# SCH_blinking-lights_2025-11-07.net
KiCad netlist of a schematic drawn in EasyEDA
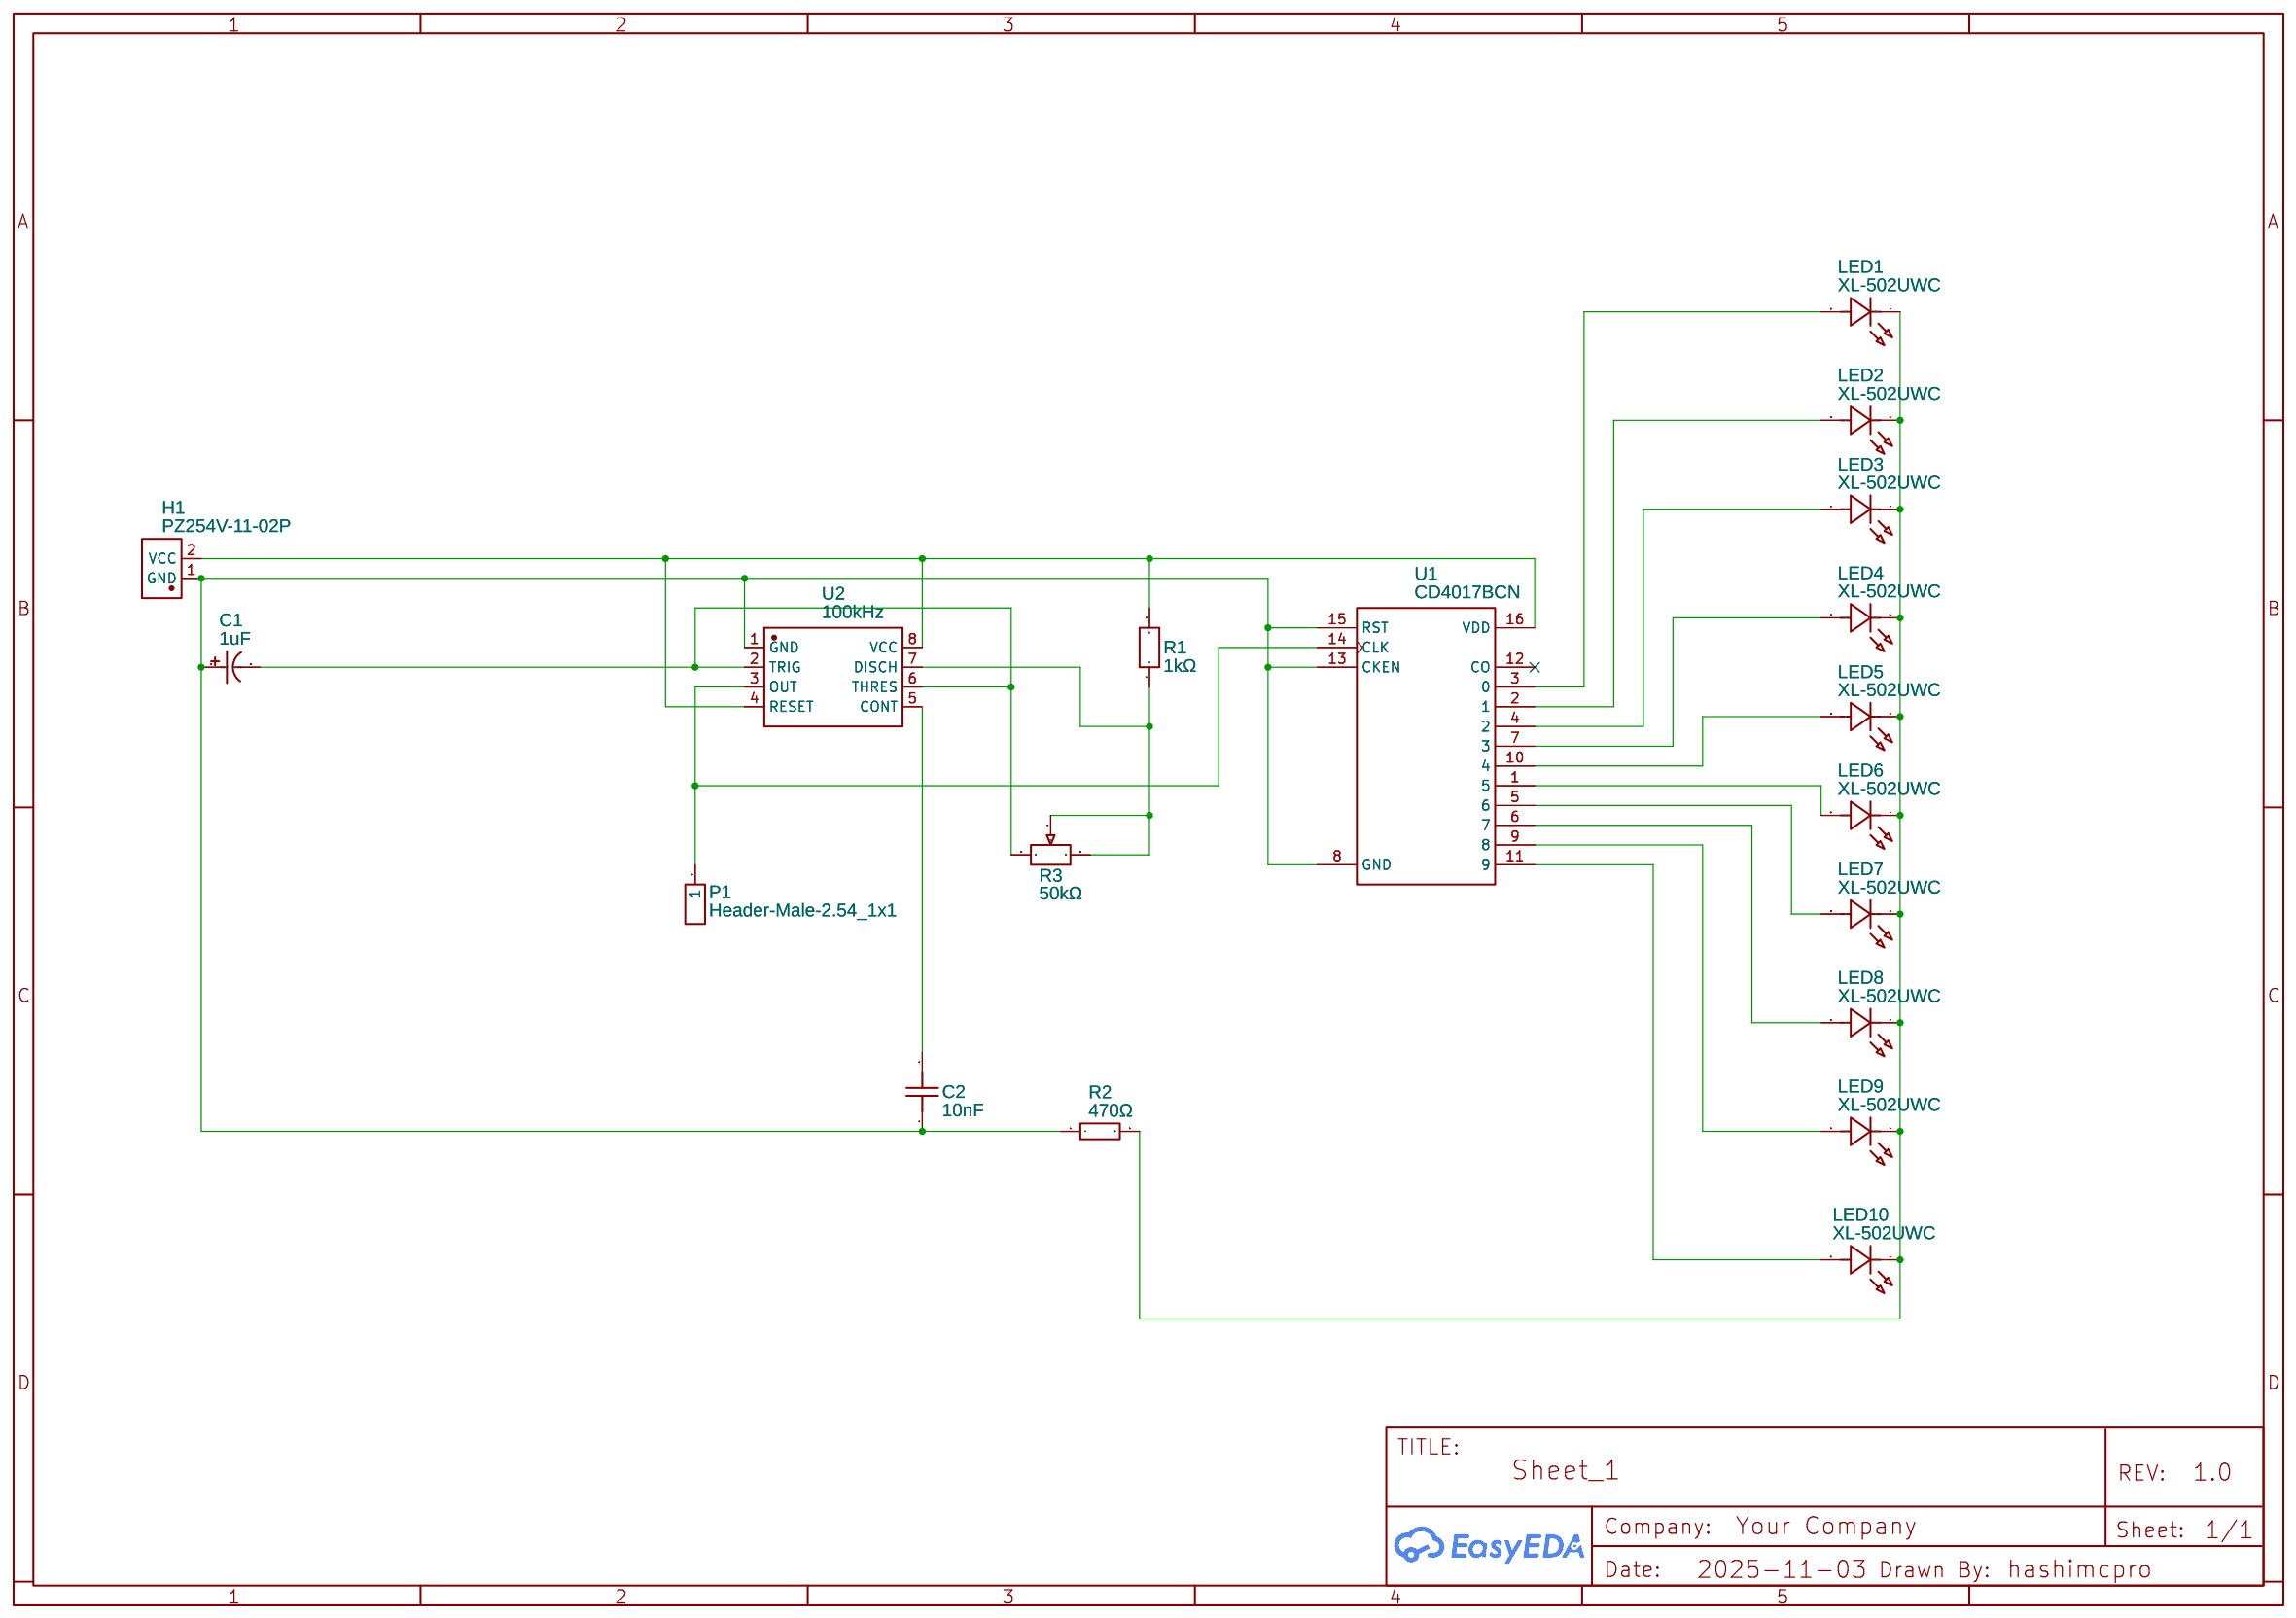
[diagram p0: schematic sheet]

(export (version "E")
  (design (tool "Eeschema 10.0.6"))
  (components
    (comp (ref "C1")
      (value "1uF")
      (fields (field (name "Manufacturer Part") "KF010M050C110A") (field (name "Manufacturer") "CapXon(丰宾)"))
      (libsource (lib "") (part "KF010M050C110A"))
    )
    (comp (ref "C2")
      (value "10nF")
      (fields (field (name "Manufacturer Part") "N09F1B103MN0B0S0N0") (field (name "Manufacturer") "STE(松田)"))
      (libsource (lib "") (part "N09F1B103MN0B0S0N0"))
    )
    (comp (ref "H1")
      (value "PZ254V-11-02P")
      (fields (field (name "Manufacturer") "XFCN(兴飞)"))
      (libsource (lib "") (part "PZ254V-11-02P"))
    )
    (comp (ref "LED1")
      (value "XL-502UWC")
      (fields (field (name "Manufacturer") "XINGLIGHT(成兴光)"))
      (libsource (lib "") (part "XL-502UWC"))
    )
    (comp (ref "LED2")
      (value "XL-502UWC")
      (fields (field (name "Manufacturer") "XINGLIGHT(成兴光)"))
      (libsource (lib "") (part "XL-502UWC"))
    )
    (comp (ref "LED3")
      (value "XL-502UWC")
      (fields (field (name "Manufacturer") "XINGLIGHT(成兴光)"))
      (libsource (lib "") (part "XL-502UWC"))
    )
    (comp (ref "LED4")
      (value "XL-502UWC")
      (fields (field (name "Manufacturer") "XINGLIGHT(成兴光)"))
      (libsource (lib "") (part "XL-502UWC"))
    )
    (comp (ref "LED5")
      (value "XL-502UWC")
      (fields (field (name "Manufacturer") "XINGLIGHT(成兴光)"))
      (libsource (lib "") (part "XL-502UWC"))
    )
    (comp (ref "LED6")
      (value "XL-502UWC")
      (fields (field (name "Manufacturer") "XINGLIGHT(成兴光)"))
      (libsource (lib "") (part "XL-502UWC"))
    )
    (comp (ref "LED7")
      (value "XL-502UWC")
      (fields (field (name "Manufacturer") "XINGLIGHT(成兴光)"))
      (libsource (lib "") (part "XL-502UWC"))
    )
    (comp (ref "LED8")
      (value "XL-502UWC")
      (fields (field (name "Manufacturer") "XINGLIGHT(成兴光)"))
      (libsource (lib "") (part "XL-502UWC"))
    )
    (comp (ref "LED9")
      (value "XL-502UWC")
      (fields (field (name "Manufacturer") "XINGLIGHT(成兴光)"))
      (libsource (lib "") (part "XL-502UWC"))
    )
    (comp (ref "LED10")
      (value "XL-502UWC")
      (fields (field (name "Manufacturer") "XINGLIGHT(成兴光)"))
      (libsource (lib "") (part "XL-502UWC"))
    )
    (comp (ref "P1")
      (value "Header-Male-2.54_1x1")
      (fields (field (name "Manufacturer Part") "2.54-1*1P针") (field (name "Manufacturer") "BOOMELE(博穆精密)"))
      (libsource (lib "") (part "Header-Male-2.54_1x1"))
    )
    (comp (ref "R1")
      (value "1kΩ")
      (fields (field (name "Manufacturer Part") "MF1/4W-1KΩ±1%T52") (field (name "Manufacturer") "华星机电"))
      (libsource (lib "") (part "MF1/4W-1KΩ±1%T52"))
    )
    (comp (ref "R2")
      (value "470Ω")
      (fields
        (field (name "Manufacturer Part") "MFR0W4F4700A50")
        (field (name "Manufacturer") "UNI-ROYAL(厚声)")
      )
      (libsource (lib "") (part "MFR0W4F4700A50"))
    )
    (comp (ref "R3")
      (value "50kΩ")
      (fields (field (name "Manufacturer Part") "3296X-1-503") (field (name "Manufacturer") "BOCHEN(博晨)"))
      (libsource (lib "") (part "3296X-1-503_C118912"))
    )
    (comp (ref "U1") (value "CD4017BCN") (libsource (lib "") (part "CD4017BCN")))
    (comp (ref "U2")
      (value "100kHz")
      (fields (field (name "Manufacturer Part") "NE555P") (field (name "Manufacturer") "TI(德州仪器)"))
      (libsource (lib "") (part "NE555P"))
    )
  )
  (nets
    (net (code "1") (name "Net-(H1-GND)") (class "Default")
      (node (ref "C1") (pin "1") (pinfunction "1_1") (pintype "input"))
      (node (ref "C2") (pin "1") (pinfunction "1_1") (pintype "unspecified"))
      (node (ref "H1") (pin "1") (pinfunction "GND_1") (pintype "unspecified"))
      (node (ref "R2") (pin "1") (pinfunction "1_1") (pintype "input"))
      (node (ref "U1") (pin "13") (pinfunction "CKEN_13") (pintype "unspecified"))
      (node (ref "U1") (pin "15") (pinfunction "RST_15") (pintype "unspecified"))
      (node (ref "U1") (pin "8") (pinfunction "GND_8") (pintype "passive"))
      (node (ref "U2") (pin "1") (pinfunction "GND_1") (pintype "unspecified"))
    )
    (net (code "2") (name "Net-(H1-VCC)") (class "Default")
      (node (ref "H1") (pin "2") (pinfunction "VCC_2") (pintype "unspecified"))
      (node (ref "R1") (pin "2") (pinfunction "2_2") (pintype "unspecified"))
      (node (ref "U1") (pin "16") (pinfunction "VDD_16") (pintype "passive"))
      (node (ref "U2") (pin "4") (pinfunction "RESET_4") (pintype "unspecified"))
      (node (ref "U2") (pin "8") (pinfunction "VCC_8") (pintype "unspecified"))
    )
    (net (code "3") (name "Net-(LED1-A)") (class "Default")
      (node (ref "LED1") (pin "2") (pinfunction "A_2") (pintype "unspecified"))
      (node (ref "U1") (pin "3") (pinfunction "0_3") (pintype "output"))
    )
    (net (code "4") (name "Net-(LED1-K)") (class "Default")
      (node (ref "LED1") (pin "1") (pinfunction "K_1") (pintype "unspecified"))
      (node (ref "LED10") (pin "1") (pinfunction "K_1") (pintype "unspecified"))
      (node (ref "LED2") (pin "1") (pinfunction "K_1") (pintype "unspecified"))
      (node (ref "LED3") (pin "1") (pinfunction "K_1") (pintype "unspecified"))
      (node (ref "LED4") (pin "1") (pinfunction "K_1") (pintype "unspecified"))
      (node (ref "LED5") (pin "1") (pinfunction "K_1") (pintype "unspecified"))
      (node (ref "LED6") (pin "1") (pinfunction "K_1") (pintype "unspecified"))
      (node (ref "LED7") (pin "1") (pinfunction "K_1") (pintype "unspecified"))
      (node (ref "LED8") (pin "1") (pinfunction "K_1") (pintype "unspecified"))
      (node (ref "LED9") (pin "1") (pinfunction "K_1") (pintype "unspecified"))
      (node (ref "R2") (pin "2") (pinfunction "2_2") (pintype "input"))
    )
    (net (code "5") (name "Net-(LED2-A)") (class "Default")
      (node (ref "LED2") (pin "2") (pinfunction "A_2") (pintype "unspecified"))
      (node (ref "U1") (pin "2") (pinfunction "1_2") (pintype "output"))
    )
    (net (code "6") (name "Net-(LED3-A)") (class "Default")
      (node (ref "LED3") (pin "2") (pinfunction "A_2") (pintype "unspecified"))
      (node (ref "U1") (pin "4") (pinfunction "2_4") (pintype "output"))
    )
    (net (code "7") (name "Net-(LED4-A)") (class "Default")
      (node (ref "LED4") (pin "2") (pinfunction "A_2") (pintype "unspecified"))
      (node (ref "U1") (pin "7") (pinfunction "3_7") (pintype "output"))
    )
    (net (code "8") (name "Net-(LED5-A)") (class "Default")
      (node (ref "LED5") (pin "2") (pinfunction "A_2") (pintype "unspecified"))
      (node (ref "U1") (pin "10") (pinfunction "4_10") (pintype "output"))
    )
    (net (code "9") (name "Net-(LED6-A)") (class "Default")
      (node (ref "LED6") (pin "2") (pinfunction "A_2") (pintype "unspecified"))
      (node (ref "U1") (pin "1") (pinfunction "5_1") (pintype "output"))
    )
    (net (code "10") (name "Net-(LED7-A)") (class "Default")
      (node (ref "LED7") (pin "2") (pinfunction "A_2") (pintype "unspecified"))
      (node (ref "U1") (pin "5") (pinfunction "6_5") (pintype "output"))
    )
    (net (code "11") (name "Net-(LED8-A)") (class "Default")
      (node (ref "LED8") (pin "2") (pinfunction "A_2") (pintype "unspecified"))
      (node (ref "U1") (pin "6") (pinfunction "7_6") (pintype "output"))
    )
    (net (code "12") (name "Net-(LED9-A)") (class "Default")
      (node (ref "LED9") (pin "2") (pinfunction "A_2") (pintype "unspecified"))
      (node (ref "U1") (pin "9") (pinfunction "8_9") (pintype "output"))
    )
    (net (code "13") (name "Net-(LED10-A)") (class "Default")
      (node (ref "LED10") (pin "2") (pinfunction "A_2") (pintype "unspecified"))
      (node (ref "U1") (pin "11") (pinfunction "9_11") (pintype "output"))
    )
    (net (code "14") (name "Net-(U1-CLK)") (class "Default")
      (node (ref "P1") (pin "1") (pinfunction "1_1") (pintype "input"))
      (node (ref "U1") (pin "14") (pinfunction "CLK_14") (pintype "unspecified"))
      (node (ref "U2") (pin "3") (pinfunction "OUT_3") (pintype "unspecified"))
    )
    (net (code "15") (name "Net-(U2-CONT)") (class "Default")
      (node (ref "C2") (pin "2") (pinfunction "2_2") (pintype "unspecified"))
      (node (ref "U2") (pin "5") (pinfunction "CONT_5") (pintype "unspecified"))
    )
    (net (code "16") (name "Net-(U2-DISCH)") (class "Default")
      (node (ref "R1") (pin "1") (pinfunction "1_1") (pintype "unspecified"))
      (node (ref "R3") (pin "2") (pinfunction "2_2") (pintype "input"))
      (node (ref "R3") (pin "3") (pinfunction "3_3") (pintype "input"))
      (node (ref "U2") (pin "7") (pinfunction "DISCH_7") (pintype "unspecified"))
    )
    (net (code "17") (name "Net-(U2-THRES)") (class "Default")
      (node (ref "C1") (pin "2") (pinfunction "2_2") (pintype "input"))
      (node (ref "R3") (pin "1") (pinfunction "1_1") (pintype "input"))
      (node (ref "U2") (pin "2") (pinfunction "TRIG_2") (pintype "unspecified"))
      (node (ref "U2") (pin "6") (pinfunction "THRES_6") (pintype "unspecified"))
    )
    (net (code "18") (name "unconnected-(U1-CO-Pad12)") (class "Default")
      (node (ref "U1") (pin "12") (pinfunction "CO_12") (pintype "output+no_connect"))
    )
  )
)
